# DAC_Diver_OPV.net
KiCad netlist of a schematic drawn in Altium Designer
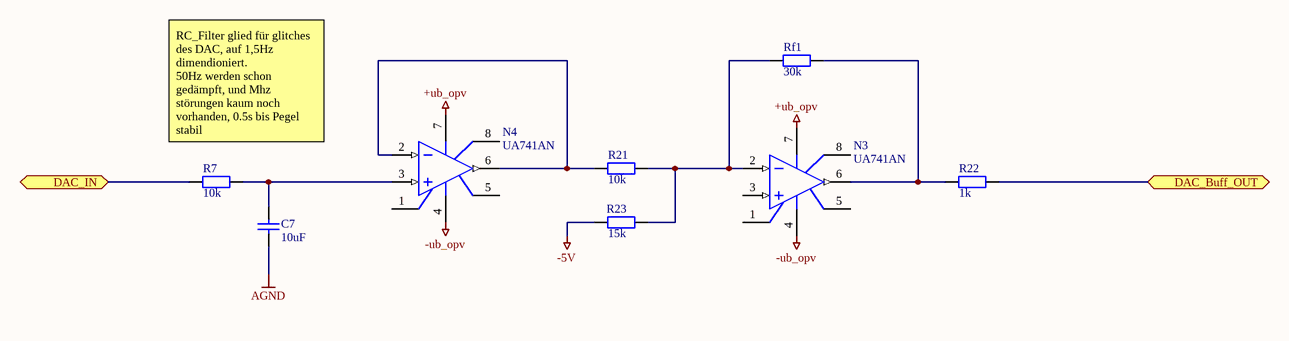
[diagram p0: DAC_Diver_OPV.SchDoc]

(export (version "E")
  (design (tool "Eeschema 10.0.6"))
  (components
    (comp (ref "C7")
      (value "10uF")
      (footprint "C1206-KUE")
      (description "Capacitor")
      (fields (field (name "MANUFACTURER") "Kemet") (field (name "PUBLISHER") "Altium Limited"))
      (libsource (lib "ExtrapartsKUE_V01") (part "Capacitor"))
    )
    (comp (ref "N3")
      (value "UA741AN")
      (footprint "DIP8")
      (description "General-Purpose Single Operational Amplifier")
      (fields (field (name "PUBLISHER") "Altium Limited"))
      (libsource (lib "ST Operational Amplifier") (part "UA741AN"))
    )
    (comp (ref "N4")
      (value "UA741AN")
      (footprint "DIP8")
      (description "General-Purpose Single Operational Amplifier")
      (fields (field (name "PUBLISHER") "Altium Limited"))
      (libsource (lib "ST Operational Amplifier") (part "UA741AN"))
    )
    (comp (ref "R7")
      (value "10k")
      (footprint "C1206-KUE")
      (description "Resistor SMD")
      (fields (field (name "MANUFACTURER") "AVX") (field (name "PUBLISHER") "Altium Limited"))
      (libsource (lib "ExtrapartsKUE_V01") (part "ResistorSMD"))
    )
    (comp (ref "R21")
      (value "10k")
      (footprint "C1206-KUE")
      (description "Resistor SMD")
      (fields (field (name "MANUFACTURER") "AVX") (field (name "PUBLISHER") "Altium Limited"))
      (libsource (lib "ExtrapartsKUE_V01") (part "ResistorSMD"))
    )
    (comp (ref "R22")
      (value "1k")
      (footprint "C1206-KUE")
      (description "Resistor SMD")
      (fields (field (name "MANUFACTURER") "AVX") (field (name "PUBLISHER") "Altium Limited"))
      (libsource (lib "ExtrapartsKUE_V01") (part "ResistorSMD"))
    )
    (comp (ref "R23")
      (value "15k")
      (footprint "C1206-KUE")
      (description "Resistor SMD")
      (fields (field (name "MANUFACTURER") "AVX") (field (name "PUBLISHER") "Altium Limited"))
      (libsource (lib "ExtrapartsKUE_V01") (part "ResistorSMD"))
    )
    (comp (ref "Rf1")
      (value "30k")
      (footprint "C1206-KUE")
      (description "Resistor SMD")
      (fields (field (name "MANUFACTURER") "AVX") (field (name "PUBLISHER") "Altium Limited"))
      (libsource (lib "ExtrapartsKUE_V01") (part "ResistorSMD"))
    )
  )
  (nets
    (net (code "1") (name "+ub_opv") (class "Default")
      (node (ref "N3") (pin "7") (pinfunction "V+_7") (pintype "power_in"))
      (node (ref "N4") (pin "7") (pinfunction "V+_7") (pintype "power_in"))
    )
    (net (code "2") (name "-5V") (class "Default")
      (node (ref "R23") (pin "2") (pinfunction "2_2") (pintype "passive"))
    )
    (net (code "3") (name "-ub_opv") (class "Default")
      (node (ref "N3") (pin "4") (pinfunction "V-_4") (pintype "power_in"))
      (node (ref "N4") (pin "4") (pinfunction "V-_4") (pintype "power_in"))
    )
    (net (code "4") (name "/DAC_Buff_OUT") (class "Default")
      (node (ref "R22") (pin "1") (pinfunction "1_1") (pintype "passive"))
    )
    (net (code "5") (name "/DAC_IN") (class "Default")
      (node (ref "R7") (pin "2") (pinfunction "2_2") (pintype "passive"))
    )
    (net (code "6") (name "AGND") (class "Default")
      (node (ref "C7") (pin "1") (pinfunction "1_1") (pintype "passive"))
    )
    (net (code "7") (name "Net-(N3-IN-)") (class "Default")
      (node (ref "N3") (pin "2") (pinfunction "IN-_2") (pintype "input"))
      (node (ref "R21") (pin "1") (pinfunction "1_1") (pintype "passive"))
      (node (ref "R23") (pin "1") (pinfunction "1_1") (pintype "passive"))
      (node (ref "Rf1") (pin "2") (pinfunction "2_2") (pintype "passive"))
    )
    (net (code "8") (name "Net-(N3-OUT)") (class "Default")
      (node (ref "N3") (pin "6") (pinfunction "OUT_6") (pintype "output"))
      (node (ref "R22") (pin "2") (pinfunction "2_2") (pintype "passive"))
      (node (ref "Rf1") (pin "1") (pinfunction "1_1") (pintype "passive"))
    )
    (net (code "9") (name "Net-(N4-IN+)") (class "Default")
      (node (ref "C7") (pin "2") (pinfunction "2_2") (pintype "passive"))
      (node (ref "N4") (pin "3") (pinfunction "IN+_3") (pintype "input"))
      (node (ref "R7") (pin "1") (pinfunction "1_1") (pintype "passive"))
    )
    (net (code "10") (name "Net-(N4-IN-)") (class "Default")
      (node (ref "N4") (pin "2") (pinfunction "IN-_2") (pintype "input"))
      (node (ref "N4") (pin "6") (pinfunction "OUT_6") (pintype "output"))
      (node (ref "R21") (pin "2") (pinfunction "2_2") (pintype "passive"))
    )
    (net (code "11") (name "unconnected-(N3-IN+-Pad3)") (class "Default")
      (node (ref "N3") (pin "3") (pinfunction "IN+_3") (pintype "input"))
    )
    (net (code "12") (name "unconnected-(N3-NC-Pad8)") (class "Default")
      (node (ref "N3") (pin "8") (pinfunction "NC_8") (pintype "passive"))
    )
    (net (code "13") (name "unconnected-(N3-OS_NULL-Pad1)") (class "Default")
      (node (ref "N3") (pin "1") (pinfunction "OS_NULL_1") (pintype "passive"))
    )
    (net (code "14") (name "unconnected-(N3-OS_NULL-Pad5)") (class "Default")
      (node (ref "N3") (pin "5") (pinfunction "OS_NULL_5") (pintype "passive"))
    )
    (net (code "15") (name "unconnected-(N4-NC-Pad8)") (class "Default")
      (node (ref "N4") (pin "8") (pinfunction "NC_8") (pintype "passive"))
    )
    (net (code "16") (name "unconnected-(N4-OS_NULL-Pad1)") (class "Default")
      (node (ref "N4") (pin "1") (pinfunction "OS_NULL_1") (pintype "passive"))
    )
    (net (code "17") (name "unconnected-(N4-OS_NULL-Pad5)") (class "Default")
      (node (ref "N4") (pin "5") (pinfunction "OS_NULL_5") (pintype "passive"))
    )
  )
)
